# lilypad_V2.net
KiCad netlist of a schematic drawn in EAGLE
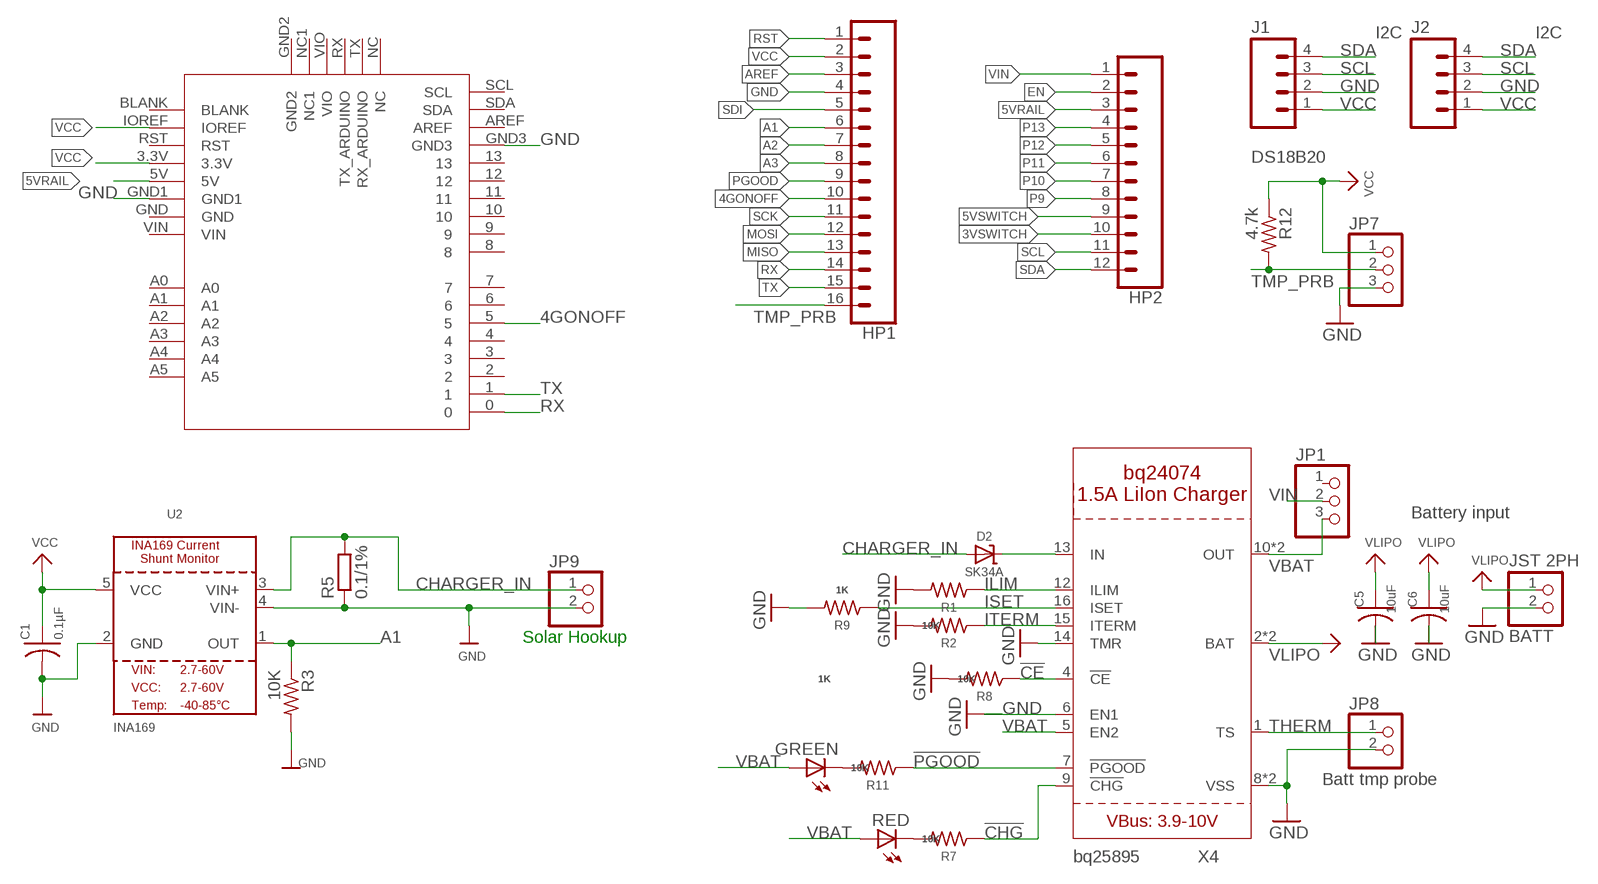
[diagram p0: schematic, sheet 1]

(export (version "E")
  (design (tool "Eeschema 10.0.6"))
  (components
    (comp (ref "BATT")
      (value "JST 2PH")
      (footprint "eagle-import:JST-PH-2-SMT-RA")
      (libsource (lib "eagle-import") (part "JST_2PIN-SMT-RA"))
    )
    (comp (ref "C1")
      (value "0.1µF")
      (footprint "eagle-import:C0805K")
      (libsource (lib "eagle-import") (part "C-USC0805K"))
    )
    (comp (ref "C5")
      (value "10uF")
      (footprint "eagle-import:C0805K")
      (libsource (lib "eagle-import") (part "C-USC0805K"))
    )
    (comp (ref "C6")
      (value "10uF")
      (footprint "eagle-import:C0805K")
      (libsource (lib "eagle-import") (part "C-USC0805K"))
    )
    (comp (ref "D2")
      (value "SK34A")
      (footprint "eagle-import:SMADIODE")
      (libsource (lib "eagle-import") (part "DIODE-SCHOTTKYSMA"))
    )
    (comp (ref "GREEN")
      (value "LEDSMT1206")
      (footprint "eagle-import:1206")
      (libsource (lib "eagle-import") (part "LEDSMT1206"))
    )
    (comp (ref "HP1")
      (value "CONN_16")
      (footprint "eagle-import:1X16")
      (libsource (lib "eagle-import") (part "CONN_16"))
    )
    (comp (ref "HP2")
      (value "CONN_12")
      (footprint "eagle-import:1X12")
      (libsource (lib "eagle-import") (part "CONN_12"))
    )
    (comp (ref "J1")
      (value "M04PTH")
      (footprint "eagle-import:1X04")
      (libsource (lib "eagle-import") (part "M04PTH"))
    )
    (comp (ref "J2")
      (value "M04PTH")
      (footprint "eagle-import:1X04")
      (libsource (lib "eagle-import") (part "M04PTH"))
    )
    (comp (ref "JP1")
      (value "PINHD-1X3")
      (footprint "eagle-import:1X03")
      (libsource (lib "eagle-import") (part "PINHD-1X3"))
    )
    (comp (ref "JP7")
      (value "PINHD-1X3")
      (footprint "eagle-import:1X03")
      (libsource (lib "eagle-import") (part "PINHD-1X3"))
    )
    (comp (ref "JP8")
      (value "PINHD-1X2")
      (footprint "eagle-import:1X02")
      (libsource (lib "eagle-import") (part "PINHD-1X2"))
    )
    (comp (ref "JP9")
      (value "PINHD-1X2")
      (footprint "eagle-import:1X02")
      (libsource (lib "eagle-import") (part "PINHD-1X2"))
    )
    (comp (ref "R1")
      (value "1K")
      (footprint "eagle-import:M0805")
      (libsource (lib "eagle-import") (part "R-US_M0805"))
    )
    (comp (ref "R2")
      (value "10K")
      (footprint "eagle-import:M0805")
      (libsource (lib "eagle-import") (part "R-US_M0805"))
    )
    (comp (ref "R3")
      (value "10K")
      (footprint "eagle-import:M0805")
      (libsource (lib "eagle-import") (part "R-US_M0805"))
    )
    (comp (ref "R5")
      (value "0.1/1%")
      (footprint "eagle-import:SMT-REF")
      (libsource (lib "eagle-import") (part "SMT-REF"))
    )
    (comp (ref "R7")
      (value "10K")
      (footprint "eagle-import:M0805")
      (libsource (lib "eagle-import") (part "R-US_M0805"))
    )
    (comp (ref "R8")
      (value "10K")
      (footprint "eagle-import:M0805")
      (libsource (lib "eagle-import") (part "R-US_M0805"))
    )
    (comp (ref "R9")
      (value "1K")
      (footprint "eagle-import:M0805")
      (libsource (lib "eagle-import") (part "R-US_M0805"))
    )
    (comp (ref "R11")
      (value "10K")
      (footprint "eagle-import:M0805")
      (libsource (lib "eagle-import") (part "R-US_M0805"))
    )
    (comp (ref "R12")
      (value "4.7k")
      (footprint "eagle-import:0805-THM")
      (libsource (lib "eagle-import") (part "FLIPFLOP-RES"))
    )
    (comp (ref "RED")
      (value "LEDSMT1206")
      (footprint "eagle-import:1206")
      (libsource (lib "eagle-import") (part "LEDSMT1206"))
    )
    (comp (ref "U$2")
      (value "LTE_BOARD")
      (footprint "eagle-import:LTE_BOARD_FOOTPRINT")
      (libsource (lib "eagle-import") (part "LTE_BOARD"))
    )
    (comp (ref "U2")
      (value "INA169")
      (footprint "eagle-import:SOT23-5")
      (libsource (lib "eagle-import") (part "INA169"))
    )
    (comp (ref "X4")
      (value "BQ24074")
      (footprint "eagle-import:QFN16_3MM")
      (libsource (lib "eagle-import") (part "BQ24074"))
    )
  )
  (nets
    (net (code "1") (name "/CHARGER_IN") (class "Default")
      (node (ref "D2") (pin "A") (pinfunction "A_A") (pintype "passive"))
      (node (ref "JP9") (pin "1") (pinfunction "1_1") (pintype "passive"))
      (node (ref "R5") (pin "1") (pinfunction "1_1") (pintype "passive"))
      (node (ref "U2") (pin "3") (pinfunction "VIN+_3") (pintype "bidirectional"))
    )
    (net (code "2") (name "/ILIM") (class "Default")
      (node (ref "R1") (pin "1") (pinfunction "1_1") (pintype "passive"))
      (node (ref "X4") (pin "12") (pinfunction "ILIM_12") (pintype "input"))
    )
    (net (code "3") (name "/ISET") (class "Default")
      (node (ref "R9") (pin "1") (pinfunction "1_1") (pintype "passive"))
      (node (ref "X4") (pin "16") (pinfunction "ISET_16") (pintype "input"))
    )
    (net (code "4") (name "/ITERM") (class "Default")
      (node (ref "R2") (pin "1") (pinfunction "1_1") (pintype "passive"))
      (node (ref "X4") (pin "15") (pinfunction "ITERM_15") (pintype "input"))
    )
    (net (code "5") (name "/THERM") (class "Default")
      (node (ref "JP8") (pin "1") (pinfunction "1_1") (pintype "passive"))
      (node (ref "X4") (pin "1") (pinfunction "TS_1") (pintype "input"))
    )
    (net (code "6") (name "/TMP_PRB") (class "Default")
      (node (ref "HP1") (pin "16") (pinfunction "16_16") (pintype "passive"))
      (node (ref "JP7") (pin "2") (pinfunction "2_2") (pintype "passive"))
      (node (ref "R12") (pin "2") (pinfunction "2_2") (pintype "passive"))
    )
    (net (code "7") (name "/VBAT") (class "Default")
      (node (ref "GREEN") (pin "A") (pinfunction "A_A") (pintype "passive"))
      (node (ref "JP1") (pin "3") (pinfunction "3_3") (pintype "passive"))
      (node (ref "RED") (pin "A") (pinfunction "A_A") (pintype "passive"))
      (node (ref "X4") (pin "10") (pinfunction "OUT_10") (pintype "output"))
      (node (ref "X4") (pin "11") (pinfunction "OUT_11") (pintype "output"))
      (node (ref "X4") (pin "5") (pinfunction "EN2_5") (pintype "input"))
    )
    (net (code "8") (name "/~{CE}") (class "Default")
      (node (ref "R8") (pin "1") (pinfunction "1_1") (pintype "passive"))
      (node (ref "X4") (pin "4") (pinfunction "~{CE}_4") (pintype "input"))
    )
    (net (code "9") (name "/~{CHG}") (class "Default")
      (node (ref "R7") (pin "1") (pinfunction "1_1") (pintype "passive"))
      (node (ref "X4") (pin "9") (pinfunction "~{CHG}_9") (pintype "output"))
    )
    (net (code "10") (name "/~{PGOOD}") (class "Default")
      (node (ref "R11") (pin "1") (pinfunction "1_1") (pintype "passive"))
      (node (ref "X4") (pin "7") (pinfunction "~{PGOOD}_7") (pintype "output"))
    )
    (net (code "11") (name "3VSWITCH") (class "Default")
      (node (ref "HP2") (pin "10") (pinfunction "10_10") (pintype "passive"))
    )
    (net (code "12") (name "4GONOFF") (class "Default")
      (node (ref "HP1") (pin "10") (pinfunction "10_10") (pintype "passive"))
      (node (ref "U$2") (pin "5") (pinfunction "5_5") (pintype "bidirectional"))
    )
    (net (code "13") (name "5VRAIL") (class "Default")
      (node (ref "HP2") (pin "3") (pinfunction "3_3") (pintype "passive"))
      (node (ref "U$2") (pin "5V") (pinfunction "5V_5V") (pintype "bidirectional"))
    )
    (net (code "14") (name "5VSWITCH") (class "Default")
      (node (ref "HP2") (pin "9") (pinfunction "9_9") (pintype "passive"))
    )
    (net (code "15") (name "A1") (class "Default")
      (node (ref "HP1") (pin "6") (pinfunction "6_6") (pintype "passive"))
      (node (ref "R3") (pin "1") (pinfunction "1_1") (pintype "passive"))
      (node (ref "U2") (pin "1") (pinfunction "OUT_1") (pintype "output"))
    )
    (net (code "16") (name "A2") (class "Default")
      (node (ref "HP1") (pin "7") (pinfunction "7_7") (pintype "passive"))
    )
    (net (code "17") (name "A3") (class "Default")
      (node (ref "HP1") (pin "8") (pinfunction "8_8") (pintype "passive"))
    )
    (net (code "18") (name "AREF") (class "Default")
      (node (ref "HP1") (pin "3") (pinfunction "3_3") (pintype "passive"))
    )
    (net (code "19") (name "EN") (class "Default")
      (node (ref "HP2") (pin "2") (pinfunction "2_2") (pintype "passive"))
    )
    (net (code "20") (name "GND") (class "Default")
      (node (ref "BATT") (pin "2") (pinfunction "1_2") (pintype "passive"))
      (node (ref "C1") (pin "2") (pinfunction "2_2") (pintype "passive"))
      (node (ref "C5") (pin "2") (pinfunction "2_2") (pintype "passive"))
      (node (ref "C6") (pin "2") (pinfunction "2_2") (pintype "passive"))
      (node (ref "HP1") (pin "4") (pinfunction "4_4") (pintype "passive"))
      (node (ref "J1") (pin "2") (pinfunction "2_2") (pintype "passive"))
      (node (ref "J2") (pin "2") (pinfunction "2_2") (pintype "passive"))
      (node (ref "JP7") (pin "3") (pinfunction "3_3") (pintype "passive"))
      (node (ref "JP8") (pin "2") (pinfunction "2_2") (pintype "passive"))
      (node (ref "JP9") (pin "2") (pinfunction "2_2") (pintype "passive"))
      (node (ref "R1") (pin "2") (pinfunction "2_2") (pintype "passive"))
      (node (ref "R2") (pin "2") (pinfunction "2_2") (pintype "passive"))
      (node (ref "R3") (pin "2") (pinfunction "2_2") (pintype "passive"))
      (node (ref "R5") (pin "2") (pinfunction "2_2") (pintype "passive"))
      (node (ref "R8") (pin "2") (pinfunction "2_2") (pintype "passive"))
      (node (ref "R9") (pin "2") (pinfunction "2_2") (pintype "passive"))
      (node (ref "U$2") (pin "GND1") (pinfunction "GND1_GND1") (pintype "bidirectional"))
      (node (ref "U$2") (pin "GND3") (pinfunction "GND3_GND3") (pintype "bidirectional"))
      (node (ref "U2") (pin "2") (pinfunction "GND_2") (pintype "power_in"))
      (node (ref "U2") (pin "4") (pinfunction "VIN-_4") (pintype "bidirectional"))
      (node (ref "X4") (pin "14") (pinfunction "TMR_14") (pintype "input"))
      (node (ref "X4") (pin "6") (pinfunction "EN1_6") (pintype "input"))
      (node (ref "X4") (pin "8") (pinfunction "VSS_8") (pintype "power_in"))
      (node (ref "X4") (pin "THERMAL") (pinfunction "VSS_THERMAL") (pintype "power_in"))
    )
    (net (code "21") (name "MISO") (class "Default")
      (node (ref "HP1") (pin "13") (pinfunction "13_13") (pintype "passive"))
    )
    (net (code "22") (name "MOSI") (class "Default")
      (node (ref "HP1") (pin "12") (pinfunction "12_12") (pintype "passive"))
    )
    (net (code "23") (name "Net-(GREEN-PadC)") (class "Default")
      (node (ref "GREEN") (pin "C") (pinfunction "C_C") (pintype "passive"))
      (node (ref "R11") (pin "2") (pinfunction "2_2") (pintype "passive"))
    )
    (net (code "24") (name "Net-(R7-Pad2)") (class "Default")
      (node (ref "R7") (pin "2") (pinfunction "2_2") (pintype "passive"))
      (node (ref "RED") (pin "C") (pinfunction "C_C") (pintype "passive"))
    )
    (net (code "25") (name "Net-(X4-IN)") (class "Default")
      (node (ref "D2") (pin "C") (pinfunction "C_C") (pintype "passive"))
      (node (ref "X4") (pin "13") (pinfunction "IN_13") (pintype "power_in"))
    )
    (net (code "26") (name "P9") (class "Default")
      (node (ref "HP2") (pin "8") (pinfunction "8_8") (pintype "passive"))
    )
    (net (code "27") (name "P10") (class "Default")
      (node (ref "HP2") (pin "7") (pinfunction "7_7") (pintype "passive"))
    )
    (net (code "28") (name "P11") (class "Default")
      (node (ref "HP2") (pin "6") (pinfunction "6_6") (pintype "passive"))
    )
    (net (code "29") (name "P12") (class "Default")
      (node (ref "HP2") (pin "5") (pinfunction "5_5") (pintype "passive"))
    )
    (net (code "30") (name "P13") (class "Default")
      (node (ref "HP2") (pin "4") (pinfunction "4_4") (pintype "passive"))
    )
    (net (code "31") (name "PGOOD") (class "Default")
      (node (ref "HP1") (pin "9") (pinfunction "9_9") (pintype "passive"))
    )
    (net (code "32") (name "RST") (class "Default")
      (node (ref "HP1") (pin "1") (pinfunction "1_1") (pintype "passive"))
    )
    (net (code "33") (name "RX") (class "Default")
      (node (ref "HP1") (pin "14") (pinfunction "14_14") (pintype "passive"))
      (node (ref "U$2") (pin "0") (pinfunction "0_0") (pintype "bidirectional"))
    )
    (net (code "34") (name "SCK") (class "Default")
      (node (ref "HP1") (pin "11") (pinfunction "11_11") (pintype "passive"))
    )
    (net (code "35") (name "SCL") (class "Default")
      (node (ref "HP2") (pin "11") (pinfunction "11_11") (pintype "passive"))
      (node (ref "J1") (pin "3") (pinfunction "3_3") (pintype "passive"))
      (node (ref "J2") (pin "3") (pinfunction "3_3") (pintype "passive"))
    )
    (net (code "36") (name "SDA") (class "Default")
      (node (ref "HP2") (pin "12") (pinfunction "12_12") (pintype "passive"))
      (node (ref "J1") (pin "4") (pinfunction "4_4") (pintype "passive"))
      (node (ref "J2") (pin "4") (pinfunction "4_4") (pintype "passive"))
    )
    (net (code "37") (name "SDI") (class "Default")
      (node (ref "HP1") (pin "5") (pinfunction "5_5") (pintype "passive"))
    )
    (net (code "38") (name "TX") (class "Default")
      (node (ref "HP1") (pin "15") (pinfunction "15_15") (pintype "passive"))
      (node (ref "U$2") (pin "1") (pinfunction "1_1") (pintype "bidirectional"))
    )
    (net (code "39") (name "VCC") (class "Default")
      (node (ref "C1") (pin "1") (pinfunction "1_1") (pintype "passive"))
      (node (ref "HP1") (pin "2") (pinfunction "2_2") (pintype "passive"))
      (node (ref "J1") (pin "1") (pinfunction "1_1") (pintype "passive"))
      (node (ref "J2") (pin "1") (pinfunction "1_1") (pintype "passive"))
      (node (ref "JP7") (pin "1") (pinfunction "1_1") (pintype "passive"))
      (node (ref "R12") (pin "1") (pinfunction "1_1") (pintype "passive"))
      (node (ref "U$2") (pin "3.3V") (pinfunction "3.3V_3.3V") (pintype "bidirectional"))
      (node (ref "U$2") (pin "IOREF") (pinfunction "IOREF_IOREF") (pintype "bidirectional"))
      (node (ref "U2") (pin "5") (pinfunction "VCC_5") (pintype "power_in"))
    )
    (net (code "40") (name "VIN") (class "Default")
      (node (ref "HP2") (pin "1") (pinfunction "1_1") (pintype "passive"))
      (node (ref "JP1") (pin "2") (pinfunction "2_2") (pintype "passive"))
    )
    (net (code "41") (name "VLIPO") (class "Default")
      (node (ref "BATT") (pin "1") (pinfunction "2_1") (pintype "passive"))
      (node (ref "C5") (pin "1") (pinfunction "1_1") (pintype "passive"))
      (node (ref "C6") (pin "1") (pinfunction "1_1") (pintype "passive"))
      (node (ref "X4") (pin "2") (pinfunction "BAT_2") (pintype "input"))
      (node (ref "X4") (pin "3") (pinfunction "BAT_3") (pintype "input"))
    )
    (net (code "42") (name "unconnected-(JP1-Pad1)") (class "Default")
      (node (ref "JP1") (pin "1") (pinfunction "1_1") (pintype "passive"))
    )
    (net (code "43") (name "unconnected-(U$2-Pad2)") (class "Default")
      (node (ref "U$2") (pin "2") (pinfunction "2_2") (pintype "bidirectional"))
    )
    (net (code "44") (name "unconnected-(U$2-Pad3)") (class "Default")
      (node (ref "U$2") (pin "3") (pinfunction "3_3") (pintype "bidirectional"))
    )
    (net (code "45") (name "unconnected-(U$2-Pad4)") (class "Default")
      (node (ref "U$2") (pin "4") (pinfunction "4_4") (pintype "bidirectional"))
    )
    (net (code "46") (name "unconnected-(U$2-Pad6)") (class "Default")
      (node (ref "U$2") (pin "6") (pinfunction "6_6") (pintype "bidirectional"))
    )
    (net (code "47") (name "unconnected-(U$2-Pad7)") (class "Default")
      (node (ref "U$2") (pin "7") (pinfunction "7_7") (pintype "bidirectional"))
    )
    (net (code "48") (name "unconnected-(U$2-Pad8)") (class "Default")
      (node (ref "U$2") (pin "8") (pinfunction "8_8") (pintype "bidirectional"))
    )
    (net (code "49") (name "unconnected-(U$2-Pad9)") (class "Default")
      (node (ref "U$2") (pin "9") (pinfunction "9_9") (pintype "bidirectional"))
    )
    (net (code "50") (name "unconnected-(U$2-Pad10)") (class "Default")
      (node (ref "U$2") (pin "10") (pinfunction "10_10") (pintype "bidirectional"))
    )
    (net (code "51") (name "unconnected-(U$2-Pad11)") (class "Default")
      (node (ref "U$2") (pin "11") (pinfunction "11_11") (pintype "bidirectional"))
    )
    (net (code "52") (name "unconnected-(U$2-Pad12)") (class "Default")
      (node (ref "U$2") (pin "12") (pinfunction "12_12") (pintype "bidirectional"))
    )
    (net (code "53") (name "unconnected-(U$2-Pad13)") (class "Default")
      (node (ref "U$2") (pin "13") (pinfunction "13_13") (pintype "bidirectional"))
    )
    (net (code "54") (name "unconnected-(U$2-PadA0)") (class "Default")
      (node (ref "U$2") (pin "A0") (pinfunction "A0_A0") (pintype "bidirectional"))
    )
    (net (code "55") (name "unconnected-(U$2-PadA1)") (class "Default")
      (node (ref "U$2") (pin "A1") (pinfunction "A1_A1") (pintype "bidirectional"))
    )
    (net (code "56") (name "unconnected-(U$2-PadA2)") (class "Default")
      (node (ref "U$2") (pin "A2") (pinfunction "A2_A2") (pintype "bidirectional"))
    )
    (net (code "57") (name "unconnected-(U$2-PadA3)") (class "Default")
      (node (ref "U$2") (pin "A3") (pinfunction "A3_A3") (pintype "bidirectional"))
    )
    (net (code "58") (name "unconnected-(U$2-PadA4)") (class "Default")
      (node (ref "U$2") (pin "A4") (pinfunction "A4_A4") (pintype "bidirectional"))
    )
    (net (code "59") (name "unconnected-(U$2-PadA5)") (class "Default")
      (node (ref "U$2") (pin "A5") (pinfunction "A5_A5") (pintype "bidirectional"))
    )
    (net (code "60") (name "unconnected-(U$2-PadAREF)") (class "Default")
      (node (ref "U$2") (pin "AREF") (pinfunction "AREF_AREF") (pintype "bidirectional"))
    )
    (net (code "61") (name "unconnected-(U$2-PadBLANK)") (class "Default")
      (node (ref "U$2") (pin "BLANK") (pinfunction "BLANK_BLANK") (pintype "bidirectional"))
    )
    (net (code "62") (name "unconnected-(U$2-PadGND)") (class "Default")
      (node (ref "U$2") (pin "GND") (pinfunction "GND_GND") (pintype "bidirectional"))
    )
    (net (code "63") (name "unconnected-(U$2-PadGND2)") (class "Default")
      (node (ref "U$2") (pin "GND2") (pinfunction "GND2_GND2") (pintype "bidirectional"))
    )
    (net (code "64") (name "unconnected-(U$2-PadNC)") (class "Default")
      (node (ref "U$2") (pin "NC") (pinfunction "NC_NC") (pintype "bidirectional"))
    )
    (net (code "65") (name "unconnected-(U$2-PadNC1)") (class "Default")
      (node (ref "U$2") (pin "NC1") (pinfunction "NC1_NC1") (pintype "bidirectional"))
    )
    (net (code "66") (name "unconnected-(U$2-PadRST)") (class "Default")
      (node (ref "U$2") (pin "RST") (pinfunction "RST_RST") (pintype "bidirectional"))
    )
    (net (code "67") (name "unconnected-(U$2-PadSCL)") (class "Default")
      (node (ref "U$2") (pin "SCL") (pinfunction "SCL_SCL") (pintype "bidirectional"))
    )
    (net (code "68") (name "unconnected-(U$2-PadSDA)") (class "Default")
      (node (ref "U$2") (pin "SDA") (pinfunction "SDA_SDA") (pintype "bidirectional"))
    )
    (net (code "69") (name "unconnected-(U$2-PadVIN)") (class "Default")
      (node (ref "U$2") (pin "VIN") (pinfunction "VIN_VIN") (pintype "bidirectional"))
    )
    (net (code "70") (name "unconnected-(U$2-PadVIO)") (class "Default")
      (node (ref "U$2") (pin "VIO") (pinfunction "VIO_VIO") (pintype "bidirectional"))
    )
    (net (code "71") (name "unconnected-(U$2-RX_ARDUINO-PadTX)") (class "Default")
      (node (ref "U$2") (pin "TX") (pinfunction "RX_ARDUINO_TX") (pintype "bidirectional"))
    )
    (net (code "72") (name "unconnected-(U$2-TX_ARDUINO-PadRX)") (class "Default")
      (node (ref "U$2") (pin "RX") (pinfunction "TX_ARDUINO_RX") (pintype "bidirectional"))
    )
  )
)
